# MachNhan.net
KiCad netlist of a schematic drawn in Altium Designer
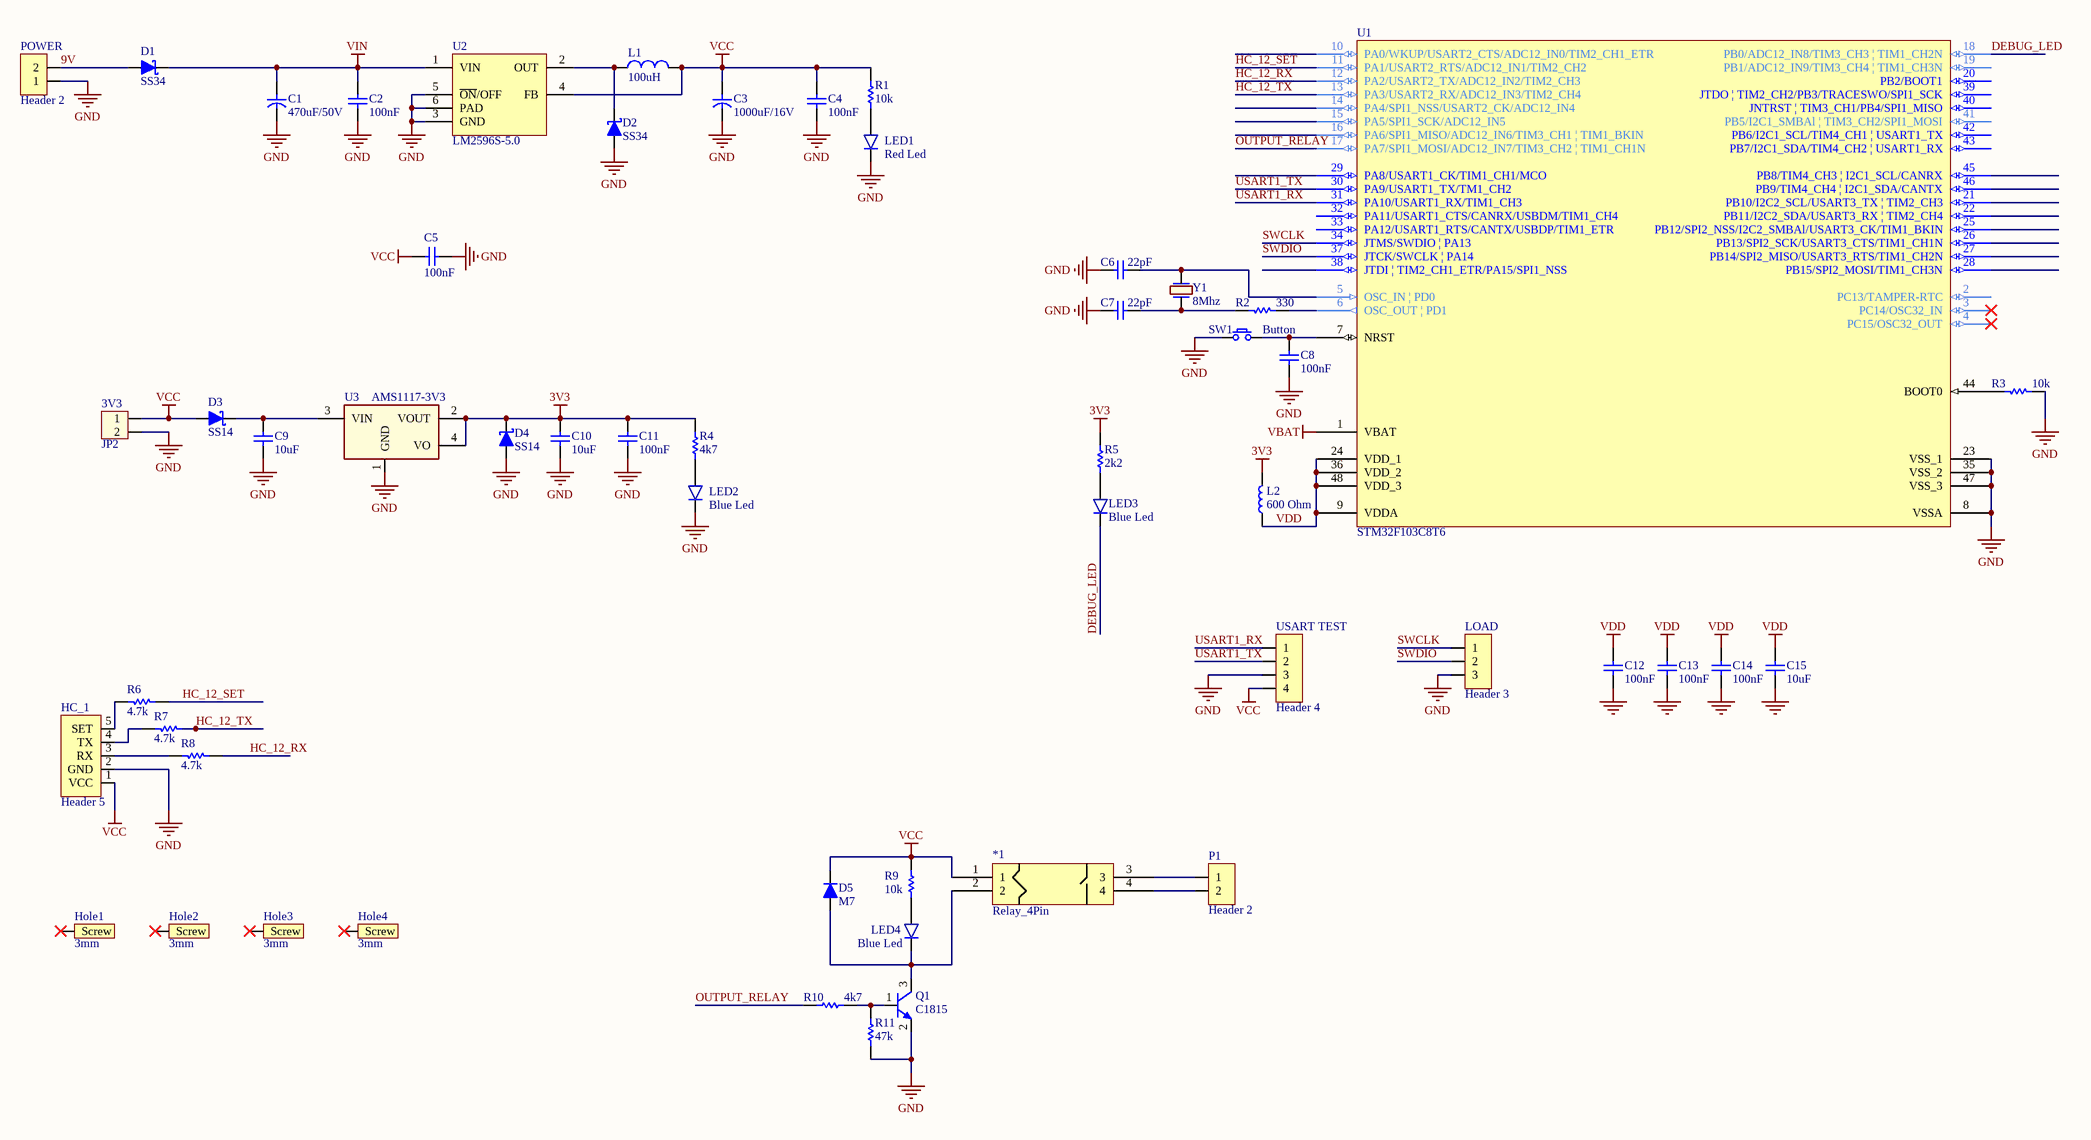
[diagram p0: MachNhan.SchDoc]

(export (version "E")
  (design (tool "Eeschema 10.0.6"))
  (components
    (comp (ref "*1")
      (value "Relay_4Pin")
      (footprint "Relay4 - duplicate")
      (libsource (lib "BKIT4U_LIB") (part "Relay_4Pin"))
    )
    (comp (ref "3V3")
      (value "JP2")
      (footprint "CON Header 2")
      (description "Connector 2")
      (libsource (lib "BKIT4U_LIB") (part "Con2"))
    )
    (comp (ref "C1")
      (value "470uF/50V")
      (footprint "CR/D.10.0x16.0/P.5.0")
      (description "Capacitor pol")
      (libsource (lib "BKIT4U_LIB") (part "Capacitor"))
    )
    (comp (ref "C2")
      (value "100nF")
      (footprint "C 0805 (2012)")
      (description "Capacitor non-pol")
      (libsource (lib "BKIT4U_LIB") (part "Capacitor NP"))
    )
    (comp (ref "C3")
      (value "1000uF/16V")
      (footprint "CR/D.10.0x12.5/P.5.0")
      (description "Capacitor pol")
      (libsource (lib "BKIT4U_LIB") (part "Capacitor"))
    )
    (comp (ref "C4")
      (value "100nF")
      (footprint "C 0805 (2012)")
      (description "Capacitor non-pol")
      (libsource (lib "BKIT4U_LIB") (part "Capacitor NP"))
    )
    (comp (ref "C5")
      (value "100nF")
      (footprint "C 0805 (2012)")
      (description "Capacitor non-pol")
      (libsource (lib "BKIT4U_LIB") (part "Capacitor NP"))
    )
    (comp (ref "C6")
      (value "22pF")
      (footprint "C 0805 (2012)")
      (description "Capacitor non-pol")
      (libsource (lib "BKIT4U_LIB") (part "Capacitor NP"))
    )
    (comp (ref "C7")
      (value "22pF")
      (footprint "C 0805 (2012)")
      (description "Capacitor non-pol")
      (libsource (lib "BKIT4U_LIB") (part "Capacitor NP"))
    )
    (comp (ref "C8")
      (value "100nF")
      (footprint "C 0805 (2012)")
      (description "Capacitor non-pol")
      (libsource (lib "BKIT4U_LIB") (part "Capacitor NP"))
    )
    (comp (ref "C9")
      (value "10uF")
      (footprint "C 0805 (2012)")
      (description "Capacitor non-pol")
      (libsource (lib "BKIT4U_LIB") (part "Capacitor NP"))
    )
    (comp (ref "C10")
      (value "10uF")
      (footprint "C 0805 (2012)")
      (description "Capacitor non-pol")
      (libsource (lib "BKIT4U_LIB") (part "Capacitor NP"))
    )
    (comp (ref "C11")
      (value "100nF")
      (footprint "C 0805 (2012)")
      (description "Capacitor non-pol")
      (libsource (lib "BKIT4U_LIB") (part "Capacitor NP"))
    )
    (comp (ref "C12")
      (value "100nF")
      (footprint "C 0805 (2012)")
      (description "Capacitor non-pol")
      (libsource (lib "BKIT4U_LIB") (part "Capacitor NP"))
    )
    (comp (ref "C13")
      (value "100nF")
      (footprint "C 0805 (2012)")
      (description "Capacitor non-pol")
      (libsource (lib "BKIT4U_LIB") (part "Capacitor NP"))
    )
    (comp (ref "C14")
      (value "100nF")
      (footprint "C 0805 (2012)")
      (description "Capacitor non-pol")
      (libsource (lib "BKIT4U_LIB") (part "Capacitor NP"))
    )
    (comp (ref "C15")
      (value "10uF")
      (footprint "C 0805 (2012)")
      (description "Capacitor non-pol")
      (libsource (lib "BKIT4U_LIB") (part "Capacitor NP"))
    )
    (comp (ref "D1")
      (value "SS34")
      (footprint "DO-214AC (SMA)")
      (description "Schottky Diode")
      (fields (field (name "PUBLISHER") "Altium Limited"))
      (libsource (lib "BKIT4U_LIB") (part "Diode Schottky"))
    )
    (comp (ref "D2")
      (value "SS34")
      (footprint "DO-214AC (SMA)")
      (description "Schottky Diode")
      (fields (field (name "PUBLISHER") "Altium Limited"))
      (libsource (lib "BKIT4U_LIB") (part "Diode Schottky"))
    )
    (comp (ref "D3")
      (value "SS14")
      (footprint "DO-214AC (SMA)")
      (description "Schottky Diode")
      (fields (field (name "PUBLISHER") "Altium Limited"))
      (libsource (lib "BKIT4U_LIB") (part "Diode Schottky"))
    )
    (comp (ref "D4")
      (value "SS14")
      (footprint "DO-214AC (SMA)")
      (description "Schottky Diode")
      (fields (field (name "PUBLISHER") "Altium Limited"))
      (libsource (lib "BKIT4U_LIB") (part "Diode Schottky"))
    )
    (comp (ref "D5")
      (value "M7")
      (footprint "DO-214AC (SMA)")
      (description "Default Diode")
      (fields (field (name "PUBLISHER") "Altium Limited"))
      (libsource (lib "BKIT4U_LIB") (part "Diode"))
    )
    (comp (ref "HC_1")
      (value "Header 5")
      (footprint "HC_12")
      (description "Header, 5-Pin")
      (fields (field (name "PUBLISHER") "Altium Limited"))
      (libsource (lib "BKIT4U_LIB") (part "HC_12"))
    )
    (comp (ref "Hole1") (value "3mm") (footprint "SCREW/3M/7M") (libsource (lib "BKIT4U_LIB") (part "Screw")))
    (comp (ref "Hole2") (value "3mm") (footprint "SCREW/3M/7M") (libsource (lib "BKIT4U_LIB") (part "Screw")))
    (comp (ref "Hole3") (value "3mm") (footprint "SCREW/3M/7M") (libsource (lib "BKIT4U_LIB") (part "Screw")))
    (comp (ref "Hole4") (value "3mm") (footprint "SCREW/3M/7M") (libsource (lib "BKIT4U_LIB") (part "Screw")))
    (comp (ref "L1")
      (value "100uH")
      (footprint "Inductor SMD 12x12x8")
      (description "Inductor")
      (libsource (lib "syhaunguyen") (part "L1"))
    )
    (comp (ref "L2")
      (value "600 Ohm")
      (footprint "Inductor SMD 0805 (2012)")
      (description "Inductor")
      (libsource (lib "BKIT4U_LIB") (part "Inductor"))
    )
    (comp (ref "LED1")
      (value "Red Led")
      (footprint "Led SMD 0805")
      (description "Typical LED")
      (libsource (lib "BKIT4U_LIB") (part "Led"))
    )
    (comp (ref "LED2")
      (value "Blue Led")
      (footprint "Led SMD 0805")
      (description "Typical LED")
      (libsource (lib "BKIT4U_LIB") (part "Led"))
    )
    (comp (ref "LED3")
      (value "Blue Led")
      (footprint "Led SMD 0805")
      (description "Typical LED")
      (libsource (lib "BKIT4U_LIB") (part "Led"))
    )
    (comp (ref "LED4")
      (value "Blue Led")
      (footprint "Led SMD 0805")
      (description "Typical LED")
      (libsource (lib "BKIT4U_LIB") (part "Led"))
    )
    (comp (ref "LOAD")
      (value "Header 3")
      (footprint "Header 3")
      (description "Header, 3-Pin")
      (libsource (lib "BKIT4U_LIB") (part "Header 3"))
    )
    (comp (ref "P1")
      (value "Header 2")
      (footprint "Header 2")
      (description "Header, 2-Pin")
      (fields (field (name "PUBLISHER") "Altium Limited"))
      (libsource (lib "") (part "Header 2_1"))
    )
    (comp (ref "POWER")
      (value "Header 2")
      (footprint "CON Header 2")
      (description "Header, 2-Pin")
      (fields (field (name "PUBLISHER") "Altium Limited"))
      (libsource (lib "BKIT4U_LIB") (part "Header 2"))
    )
    (comp (ref "Q1")
      (value "C1815")
      (footprint "SOT-23")
      (description "NPN Bipolar Transistor")
      (libsource (lib "BKIT4U_LIB") (part "Transistor NPN"))
    )
    (comp (ref "R1")
      (value "10k")
      (footprint "R 0805 (2012)")
      (description "Resistor")
      (fields (field (name "PUBLISHER") "Altium Limited"))
      (libsource (lib "BKIT4U_LIB") (part "Resistor"))
    )
    (comp (ref "R2")
      (value "330")
      (footprint "R 0805 (2012)")
      (description "Resistor")
      (fields (field (name "PUBLISHER") "Altium Limited"))
      (libsource (lib "BKIT4U_LIB") (part "Resistor"))
    )
    (comp (ref "R3")
      (value "10k")
      (footprint "R 0805 (2012)")
      (description "Resistor")
      (fields (field (name "PUBLISHER") "Altium Limited"))
      (libsource (lib "BKIT4U_LIB") (part "Resistor"))
    )
    (comp (ref "R4")
      (value "4k7")
      (footprint "R 0805 (2012)")
      (description "Resistor")
      (fields (field (name "PUBLISHER") "Altium Limited"))
      (libsource (lib "BKIT4U_LIB") (part "Resistor"))
    )
    (comp (ref "R5")
      (value "2k2")
      (footprint "R 0805 (2012)")
      (description "Resistor")
      (fields (field (name "PUBLISHER") "Altium Limited"))
      (libsource (lib "BKIT4U_LIB") (part "Resistor"))
    )
    (comp (ref "R6")
      (value "4.7k")
      (footprint "R 0805 (2012)")
      (description "Resistor")
      (fields (field (name "PUBLISHER") "Altium Limited"))
      (libsource (lib "BKIT4U_LIB") (part "Resistor"))
    )
    (comp (ref "R7")
      (value "4.7k")
      (footprint "R 0805 (2012)")
      (description "Resistor")
      (fields (field (name "PUBLISHER") "Altium Limited"))
      (libsource (lib "BKIT4U_LIB") (part "Resistor"))
    )
    (comp (ref "R8")
      (value "4.7k")
      (footprint "R 0805 (2012)")
      (description "Resistor")
      (fields (field (name "PUBLISHER") "Altium Limited"))
      (libsource (lib "BKIT4U_LIB") (part "Resistor"))
    )
    (comp (ref "R9")
      (value "10k")
      (footprint "R 0805 (2012)")
      (description "Resistor")
      (fields (field (name "PUBLISHER") "Altium Limited"))
      (libsource (lib "BKIT4U_LIB") (part "Resistor"))
    )
    (comp (ref "R10")
      (value "4k7")
      (footprint "R 0805 (2012)")
      (description "Resistor")
      (fields (field (name "PUBLISHER") "Altium Limited"))
      (libsource (lib "BKIT4U_LIB") (part "Resistor"))
    )
    (comp (ref "R11")
      (value "47k")
      (footprint "R 0805 (2012)")
      (description "Resistor")
      (fields (field (name "PUBLISHER") "Altium Limited"))
      (libsource (lib "BKIT4U_LIB") (part "Resistor"))
    )
    (comp (ref "SW1")
      (value "Button")
      (footprint "SW/2/SMD")
      (description "Tact switch 2 pin")
      (libsource (lib "BKIT4U_LIB") (part "SW SPST"))
    )
    (comp (ref "U1")
      (value "STM32F103C8T6")
      (footprint "LQFP48_N")
      (description "STM32 ARM-based 32-bit MCU with 64 Kbytes Flash, 48-pin LQFP, Industrial Temperature")
      (fields (field (name "PUBLISHER") "Altium Limited"))
      (libsource (lib "BKIT4U_LIB") (part "STM32F103C8T6"))
    )
    (comp (ref "U2")
      (value "LM2596S-5.0")
      (footprint "TO-263-5")
      (description "SIMPLE SWITCHER® 3A Step-Down Voltage Regulator")
      (libsource (lib "BKIT4U_LIB") (part "LM2576/96"))
    )
    (comp (ref "U3")
      (value "AMS1117-3V3")
      (footprint "SOT-223")
      (description "1A LDO Voltage Regulator, ADJ or fixed 1.5/1.8/2.5/2.85/3.3/5V")
      (libsource (lib "BKIT4U_LIB") (part "AMS1117"))
    )
    (comp (ref "USART TEST")
      (value "Header 4")
      (footprint "CON Header 4")
      (description "Header, 4-Pin")
      (libsource (lib "BKIT4U_LIB") (part "Header 4"))
    )
    (comp (ref "Y1")
      (value "8Mhz")
      (footprint "Crystal HC49US SMD")
      (libsource (lib "BKIT4U_LIB") (part "Crystal"))
    )
  )
  (nets
    (net (code "1") (name "/9V") (class "Default")
      (node (ref "D1") (pin "1") (pinfunction "A_1") (pintype "passive"))
      (node (ref "POWER") (pin "2") (pinfunction "2_2") (pintype "passive"))
    )
    (net (code "2") (name "/DEBUG_LED") (class "Default")
      (node (ref "LED3") (pin "2") (pinfunction "K_2") (pintype "passive"))
      (node (ref "U1") (pin "18") (pinfunction "PB0/ADC12_IN8/TIM3_CH3_¦_TIM1_CH2N_18") (pintype "bidirectional"))
    )
    (net (code "3") (name "/HC_12_RX") (class "Default")
      (node (ref "R8") (pin "2") (pinfunction "2_2") (pintype "passive"))
      (node (ref "U1") (pin "12") (pinfunction "PA2/USART2_TX/ADC12_IN2/TIM2_CH3_12") (pintype "bidirectional"))
    )
    (net (code "4") (name "/HC_12_SET") (class "Default")
      (node (ref "R6") (pin "2") (pinfunction "2_2") (pintype "passive"))
      (node (ref "U1") (pin "11") (pinfunction "PA1/USART2_RTS/ADC12_IN1/TIM2_CH2_11") (pintype "bidirectional"))
    )
    (net (code "5") (name "/HC_12_TX") (class "Default")
      (node (ref "R7") (pin "2") (pinfunction "2_2") (pintype "passive"))
      (node (ref "U1") (pin "13") (pinfunction "PA3/USART2_RX/ADC12_IN3/TIM2_CH4_13") (pintype "bidirectional"))
    )
    (net (code "6") (name "/OUTPUT_RELAY") (class "Default")
      (node (ref "R10") (pin "1") (pinfunction "1_1") (pintype "passive"))
      (node (ref "U1") (pin "17") (pinfunction "PA7/SPI1_MOSI/ADC12_IN7/TIM3_CH2_¦_TIM1_CH1N_17") (pintype "bidirectional"))
    )
    (net (code "7") (name "/SWCLK") (class "Default")
      (node (ref "LOAD") (pin "1") (pinfunction "1_1") (pintype "passive"))
      (node (ref "U1") (pin "34") (pinfunction "JTMS/SWDIO_¦_PA13_34") (pintype "bidirectional"))
    )
    (net (code "8") (name "/SWDIO") (class "Default")
      (node (ref "LOAD") (pin "2") (pinfunction "2_2") (pintype "passive"))
      (node (ref "U1") (pin "37") (pinfunction "JTCK/SWCLK_¦_PA14_37") (pintype "bidirectional"))
    )
    (net (code "9") (name "/USART1_RX") (class "Default")
      (node (ref "U1") (pin "31") (pinfunction "PA10/USART1_RX/TIM1_CH3_31") (pintype "bidirectional"))
      (node (ref "USART TEST") (pin "1") (pinfunction "1_1") (pintype "passive"))
    )
    (net (code "10") (name "/USART1_TX") (class "Default")
      (node (ref "U1") (pin "30") (pinfunction "PA9/USART1_TX/TM1_CH2_30") (pintype "bidirectional"))
      (node (ref "USART TEST") (pin "2") (pinfunction "2_2") (pintype "passive"))
    )
    (net (code "11") (name "3V3") (class "Default")
      (node (ref "C10") (pin "1") (pinfunction "1_1") (pintype "passive"))
      (node (ref "C11") (pin "1") (pinfunction "1_1") (pintype "passive"))
      (node (ref "D4") (pin "2") (pinfunction "K_2") (pintype "passive"))
      (node (ref "L2") (pin "2") (pinfunction "2_2") (pintype "passive"))
      (node (ref "R4") (pin "2") (pinfunction "2_2") (pintype "passive"))
      (node (ref "R5") (pin "2") (pinfunction "2_2") (pintype "passive"))
      (node (ref "U3") (pin "2") (pinfunction "VOUT_2") (pintype "passive"))
      (node (ref "U3") (pin "4") (pinfunction "VO_4") (pintype "passive"))
    )
    (net (code "12") (name "GND") (class "Default")
      (node (ref "3V3") (pin "2") (pinfunction "2_2") (pintype "passive"))
      (node (ref "C1") (pin "2") (pinfunction "2_2") (pintype "passive"))
      (node (ref "C10") (pin "2") (pinfunction "2_2") (pintype "passive"))
      (node (ref "C11") (pin "2") (pinfunction "2_2") (pintype "passive"))
      (node (ref "C12") (pin "2") (pinfunction "2_2") (pintype "passive"))
      (node (ref "C13") (pin "2") (pinfunction "2_2") (pintype "passive"))
      (node (ref "C14") (pin "2") (pinfunction "2_2") (pintype "passive"))
      (node (ref "C15") (pin "2") (pinfunction "2_2") (pintype "passive"))
      (node (ref "C2") (pin "2") (pinfunction "2_2") (pintype "passive"))
      (node (ref "C3") (pin "2") (pinfunction "2_2") (pintype "passive"))
      (node (ref "C4") (pin "2") (pinfunction "2_2") (pintype "passive"))
      (node (ref "C5") (pin "1") (pinfunction "1_1") (pintype "passive"))
      (node (ref "C6") (pin "2") (pinfunction "2_2") (pintype "passive"))
      (node (ref "C7") (pin "2") (pinfunction "2_2") (pintype "passive"))
      (node (ref "C8") (pin "2") (pinfunction "2_2") (pintype "passive"))
      (node (ref "C9") (pin "2") (pinfunction "2_2") (pintype "passive"))
      (node (ref "D2") (pin "1") (pinfunction "A_1") (pintype "passive"))
      (node (ref "D4") (pin "1") (pinfunction "A_1") (pintype "passive"))
      (node (ref "HC_1") (pin "2") (pinfunction "GND_2") (pintype "passive"))
      (node (ref "LED1") (pin "2") (pinfunction "K_2") (pintype "passive"))
      (node (ref "LED2") (pin "2") (pinfunction "K_2") (pintype "passive"))
      (node (ref "LOAD") (pin "3") (pinfunction "3_3") (pintype "passive"))
      (node (ref "POWER") (pin "1") (pinfunction "1_1") (pintype "passive"))
      (node (ref "Q1") (pin "2") (pinfunction "E_2") (pintype "passive"))
      (node (ref "R11") (pin "1") (pinfunction "1_1") (pintype "passive"))
      (node (ref "R3") (pin "1") (pinfunction "1_1") (pintype "passive"))
      (node (ref "SW1") (pin "1") (pinfunction "1_1") (pintype "passive"))
      (node (ref "U1") (pin "23") (pinfunction "VSS_1_23") (pintype "power_in"))
      (node (ref "U1") (pin "35") (pinfunction "VSS_2_35") (pintype "power_in"))
      (node (ref "U1") (pin "47") (pinfunction "VSS_3_47") (pintype "power_in"))
      (node (ref "U1") (pin "8") (pinfunction "VSSA_8") (pintype "power_in"))
      (node (ref "U2") (pin "3") (pinfunction "GND_3") (pintype "passive"))
      (node (ref "U2") (pin "5") (pinfunction "~{ON}/OFF_5") (pintype "passive"))
      (node (ref "U2") (pin "6") (pinfunction "PAD_6") (pintype "passive"))
      (node (ref "U3") (pin "1") (pinfunction "GND_1") (pintype "passive"))
      (node (ref "USART TEST") (pin "3") (pinfunction "3_3") (pintype "passive"))
    )
    (net (code "13") (name "Net-(*1-Pad3)") (class "Default")
      (node (ref "*1") (pin "3") (pinfunction "3_3") (pintype "passive"))
      (node (ref "P1") (pin "1") (pinfunction "1_1") (pintype "passive"))
    )
    (net (code "14") (name "Net-(*1-Pad4)") (class "Default")
      (node (ref "*1") (pin "4") (pinfunction "4_4") (pintype "passive"))
      (node (ref "P1") (pin "2") (pinfunction "2_2") (pintype "passive"))
    )
    (net (code "15") (name "Net-(C7-Pad1)") (class "Default")
      (node (ref "C7") (pin "1") (pinfunction "1_1") (pintype "passive"))
      (node (ref "R2") (pin "2") (pinfunction "2_2") (pintype "passive"))
      (node (ref "Y1") (pin "1") (pinfunction "1_1") (pintype "passive"))
    )
    (net (code "16") (name "Net-(D2-K)") (class "Default")
      (node (ref "D2") (pin "2") (pinfunction "K_2") (pintype "passive"))
      (node (ref "L1") (pin "1") (pinfunction "1_1") (pintype "passive"))
      (node (ref "U2") (pin "2") (pinfunction "OUT_2") (pintype "passive"))
    )
    (net (code "17") (name "Net-(D3-K)") (class "Default")
      (node (ref "C9") (pin "1") (pinfunction "1_1") (pintype "passive"))
      (node (ref "D3") (pin "2") (pinfunction "K_2") (pintype "passive"))
      (node (ref "U3") (pin "3") (pinfunction "VIN_3") (pintype "power_in"))
    )
    (net (code "18") (name "Net-(D5-A)") (class "Default")
      (node (ref "*1") (pin "2") (pinfunction "2_2") (pintype "passive"))
      (node (ref "D5") (pin "1") (pinfunction "A_1") (pintype "passive"))
      (node (ref "LED4") (pin "2") (pinfunction "K_2") (pintype "passive"))
      (node (ref "Q1") (pin "3") (pinfunction "C_3") (pintype "passive"))
    )
    (net (code "19") (name "Net-(HC_1-RX)") (class "Default")
      (node (ref "HC_1") (pin "3") (pinfunction "RX_3") (pintype "passive"))
      (node (ref "R8") (pin "1") (pinfunction "1_1") (pintype "passive"))
    )
    (net (code "20") (name "Net-(HC_1-SET)") (class "Default")
      (node (ref "HC_1") (pin "5") (pinfunction "SET_5") (pintype "passive"))
      (node (ref "R6") (pin "1") (pinfunction "1_1") (pintype "passive"))
    )
    (net (code "21") (name "Net-(HC_1-TX)") (class "Default")
      (node (ref "HC_1") (pin "4") (pinfunction "TX_4") (pintype "passive"))
      (node (ref "R7") (pin "1") (pinfunction "1_1") (pintype "passive"))
    )
    (net (code "22") (name "Net-(LED1-A)") (class "Default")
      (node (ref "LED1") (pin "1") (pinfunction "A_1") (pintype "passive"))
      (node (ref "R1") (pin "1") (pinfunction "1_1") (pintype "passive"))
    )
    (net (code "23") (name "Net-(LED2-A)") (class "Default")
      (node (ref "LED2") (pin "1") (pinfunction "A_1") (pintype "passive"))
      (node (ref "R4") (pin "1") (pinfunction "1_1") (pintype "passive"))
    )
    (net (code "24") (name "Net-(LED3-A)") (class "Default")
      (node (ref "LED3") (pin "1") (pinfunction "A_1") (pintype "passive"))
      (node (ref "R5") (pin "1") (pinfunction "1_1") (pintype "passive"))
    )
    (net (code "25") (name "Net-(LED4-A)") (class "Default")
      (node (ref "LED4") (pin "1") (pinfunction "A_1") (pintype "passive"))
      (node (ref "R9") (pin "1") (pinfunction "1_1") (pintype "passive"))
    )
    (net (code "26") (name "Net-(Q1-B)") (class "Default")
      (node (ref "Q1") (pin "1") (pinfunction "B_1") (pintype "passive"))
      (node (ref "R10") (pin "2") (pinfunction "2_2") (pintype "passive"))
      (node (ref "R11") (pin "2") (pinfunction "2_2") (pintype "passive"))
    )
    (net (code "27") (name "Net-(U1-BOOT0)") (class "Default")
      (node (ref "R3") (pin "2") (pinfunction "2_2") (pintype "passive"))
      (node (ref "U1") (pin "44") (pinfunction "BOOT0_44") (pintype "input"))
    )
    (net (code "28") (name "Net-(U1-NRST)") (class "Default")
      (node (ref "C8") (pin "1") (pinfunction "1_1") (pintype "passive"))
      (node (ref "SW1") (pin "2") (pinfunction "2_2") (pintype "passive"))
      (node (ref "U1") (pin "7") (pinfunction "NRST_7") (pintype "bidirectional"))
    )
    (net (code "29") (name "Net-(U1-OSC_IN_¦_PD0)") (class "Default")
      (node (ref "C6") (pin "1") (pinfunction "1_1") (pintype "passive"))
      (node (ref "U1") (pin "5") (pinfunction "OSC_IN_¦_PD0_5") (pintype "input"))
      (node (ref "Y1") (pin "2") (pinfunction "2_2") (pintype "passive"))
    )
    (net (code "30") (name "Net-(U1-OSC_OUT_¦_PD1)") (class "Default")
      (node (ref "R2") (pin "1") (pinfunction "1_1") (pintype "passive"))
      (node (ref "U1") (pin "6") (pinfunction "OSC_OUT_¦_PD1_6") (pintype "output"))
    )
    (net (code "31") (name "VBAT") (class "Default")
      (node (ref "U1") (pin "1") (pinfunction "VBAT_1") (pintype "power_in"))
    )
    (net (code "32") (name "VCC") (class "Default")
      (node (ref "*1") (pin "1") (pinfunction "1_1") (pintype "passive"))
      (node (ref "3V3") (pin "1") (pinfunction "1_1") (pintype "passive"))
      (node (ref "C3") (pin "1") (pinfunction "1_1") (pintype "passive"))
      (node (ref "C4") (pin "1") (pinfunction "1_1") (pintype "passive"))
      (node (ref "C5") (pin "2") (pinfunction "2_2") (pintype "passive"))
      (node (ref "D3") (pin "1") (pinfunction "A_1") (pintype "passive"))
      (node (ref "D5") (pin "2") (pinfunction "K_2") (pintype "passive"))
      (node (ref "HC_1") (pin "1") (pinfunction "VCC_1") (pintype "passive"))
      (node (ref "L1") (pin "2") (pinfunction "2_2") (pintype "passive"))
      (node (ref "R1") (pin "2") (pinfunction "2_2") (pintype "passive"))
      (node (ref "R9") (pin "2") (pinfunction "2_2") (pintype "passive"))
      (node (ref "U2") (pin "4") (pinfunction "FB_4") (pintype "passive"))
      (node (ref "USART TEST") (pin "4") (pinfunction "4_4") (pintype "passive"))
    )
    (net (code "33") (name "VDD") (class "Default")
      (node (ref "C12") (pin "1") (pinfunction "1_1") (pintype "passive"))
      (node (ref "C13") (pin "1") (pinfunction "1_1") (pintype "passive"))
      (node (ref "C14") (pin "1") (pinfunction "1_1") (pintype "passive"))
      (node (ref "C15") (pin "1") (pinfunction "1_1") (pintype "passive"))
      (node (ref "L2") (pin "1") (pinfunction "1_1") (pintype "passive"))
      (node (ref "U1") (pin "24") (pinfunction "VDD_1_24") (pintype "power_in"))
      (node (ref "U1") (pin "36") (pinfunction "VDD_2_36") (pintype "power_in"))
      (node (ref "U1") (pin "48") (pinfunction "VDD_3_48") (pintype "power_in"))
      (node (ref "U1") (pin "9") (pinfunction "VDDA_9") (pintype "power_in"))
    )
    (net (code "34") (name "VIN") (class "Default")
      (node (ref "C1") (pin "1") (pinfunction "1_1") (pintype "passive"))
      (node (ref "C2") (pin "1") (pinfunction "1_1") (pintype "passive"))
      (node (ref "D1") (pin "2") (pinfunction "K_2") (pintype "passive"))
      (node (ref "U2") (pin "1") (pinfunction "VIN_1") (pintype "passive"))
    )
    (net (code "35") (name "unconnected-(Hole1-Screw-Pad1)") (class "Default")
      (node (ref "Hole1") (pin "1") (pinfunction "Screw_1") (pintype "passive+no_connect"))
    )
    (net (code "36") (name "unconnected-(Hole2-Screw-Pad1)") (class "Default")
      (node (ref "Hole2") (pin "1") (pinfunction "Screw_1") (pintype "passive+no_connect"))
    )
    (net (code "37") (name "unconnected-(Hole3-Screw-Pad1)") (class "Default")
      (node (ref "Hole3") (pin "1") (pinfunction "Screw_1") (pintype "passive+no_connect"))
    )
    (net (code "38") (name "unconnected-(Hole4-Screw-Pad1)") (class "Default")
      (node (ref "Hole4") (pin "1") (pinfunction "Screw_1") (pintype "passive+no_connect"))
    )
    (net (code "39") (name "unconnected-(U1-JNTRST_¦_TIM3_CH1{slash}PB4{slash}SPI1_MISO-Pad40)") (class "Default")
      (node (ref "U1") (pin "40") (pinfunction "JNTRST_¦_TIM3_CH1/PB4/SPI1_MISO_40") (pintype "bidirectional"))
    )
    (net (code "40") (name "unconnected-(U1-JTDI_¦_TIM2_CH1_ETR{slash}PA15{slash}SPI1_NSS-Pad38)") (class "Default")
      (node (ref "U1") (pin "38") (pinfunction "JTDI_¦_TIM2_CH1_ETR/PA15/SPI1_NSS_38") (pintype "bidirectional"))
    )
    (net (code "41") (name "unconnected-(U1-JTDO_¦_TIM2_CH2{slash}PB3{slash}TRACESWO{slash}SPI1_SCK-Pad39)") (class "Default")
      (node (ref "U1") (pin "39") (pinfunction "JTDO_¦_TIM2_CH2/PB3/TRACESWO/SPI1_SCK_39") (pintype "bidirectional"))
    )
    (net (code "42") (name "unconnected-(U1-PA0{slash}WKUP{slash}USART2_CTS{slash}ADC12_IN0{slash}TIM2_CH1_ETR-Pad10)") (class "Default")
      (node (ref "U1") (pin "10") (pinfunction "PA0/WKUP/USART2_CTS/ADC12_IN0/TIM2_CH1_ETR_10") (pintype "bidirectional"))
    )
    (net (code "43") (name "unconnected-(U1-PA4{slash}SPI1_NSS{slash}USART2_CK{slash}ADC12_IN4-Pad14)") (class "Default")
      (node (ref "U1") (pin "14") (pinfunction "PA4/SPI1_NSS/USART2_CK/ADC12_IN4_14") (pintype "bidirectional"))
    )
    (net (code "44") (name "unconnected-(U1-PA5{slash}SPI1_SCK{slash}ADC12_IN5-Pad15)") (class "Default")
      (node (ref "U1") (pin "15") (pinfunction "PA5/SPI1_SCK/ADC12_IN5_15") (pintype "bidirectional"))
    )
    (net (code "45") (name "unconnected-(U1-PA6{slash}SPI1_MISO{slash}ADC12_IN6{slash}TIM3_CH1_¦_TIM1_BKIN-Pad16)") (class "Default")
      (node (ref "U1") (pin "16") (pinfunction "PA6/SPI1_MISO/ADC12_IN6/TIM3_CH1_¦_TIM1_BKIN_16") (pintype "bidirectional"))
    )
    (net (code "46") (name "unconnected-(U1-PA8{slash}USART1_CK{slash}TIM1_CH1{slash}MCO-Pad29)") (class "Default")
      (node (ref "U1") (pin "29") (pinfunction "PA8/USART1_CK/TIM1_CH1/MCO_29") (pintype "bidirectional"))
    )
    (net (code "47") (name "unconnected-(U1-PA11{slash}USART1_CTS{slash}CANRX{slash}USBDM{slash}TIM1_CH4-Pad32)") (class "Default")
      (node (ref "U1") (pin "32") (pinfunction "PA11/USART1_CTS/CANRX/USBDM/TIM1_CH4_32") (pintype "bidirectional"))
    )
    (net (code "48") (name "unconnected-(U1-PA12{slash}USART1_RTS{slash}CANTX{slash}USBDP{slash}TIM1_ETR-Pad33)") (class "Default")
      (node (ref "U1") (pin "33") (pinfunction "PA12/USART1_RTS/CANTX/USBDP/TIM1_ETR_33") (pintype "bidirectional"))
    )
    (net (code "49") (name "unconnected-(U1-PB1{slash}ADC12_IN9{slash}TIM3_CH4_¦_TIM1_CH3N-Pad19)") (class "Default")
      (node (ref "U1") (pin "19") (pinfunction "PB1/ADC12_IN9/TIM3_CH4_¦_TIM1_CH3N_19") (pintype "bidirectional"))
    )
    (net (code "50") (name "unconnected-(U1-PB2{slash}BOOT1-Pad20)") (class "Default")
      (node (ref "U1") (pin "20") (pinfunction "PB2/BOOT1_20") (pintype "bidirectional"))
    )
    (net (code "51") (name "unconnected-(U1-PB5{slash}I2C1_SMBAl_¦_TIM3_CH2{slash}SPI1_MOSI-Pad41)") (class "Default")
      (node (ref "U1") (pin "41") (pinfunction "PB5/I2C1_SMBAl_¦_TIM3_CH2/SPI1_MOSI_41") (pintype "bidirectional"))
    )
    (net (code "52") (name "unconnected-(U1-PB6{slash}I2C1_SCL{slash}TIM4_CH1_¦_USART1_TX-Pad42)") (class "Default")
      (node (ref "U1") (pin "42") (pinfunction "PB6/I2C1_SCL/TIM4_CH1_¦_USART1_TX_42") (pintype "bidirectional"))
    )
    (net (code "53") (name "unconnected-(U1-PB7{slash}I2C1_SDA{slash}TIM4_CH2_¦_USART1_RX-Pad43)") (class "Default")
      (node (ref "U1") (pin "43") (pinfunction "PB7/I2C1_SDA/TIM4_CH2_¦_USART1_RX_43") (pintype "bidirectional"))
    )
    (net (code "54") (name "unconnected-(U1-PB8{slash}TIM4_CH3_¦_I2C1_SCL{slash}CANRX-Pad45)") (class "Default")
      (node (ref "U1") (pin "45") (pinfunction "PB8/TIM4_CH3_¦_I2C1_SCL/CANRX_45") (pintype "bidirectional"))
    )
    (net (code "55") (name "unconnected-(U1-PB9{slash}TIM4_CH4_¦_I2C1_SDA{slash}CANTX-Pad46)") (class "Default")
      (node (ref "U1") (pin "46") (pinfunction "PB9/TIM4_CH4_¦_I2C1_SDA/CANTX_46") (pintype "bidirectional"))
    )
    (net (code "56") (name "unconnected-(U1-PB10{slash}I2C2_SCL{slash}USART3_TX_¦_TIM2_CH3-Pad21)") (class "Default")
      (node (ref "U1") (pin "21") (pinfunction "PB10/I2C2_SCL/USART3_TX_¦_TIM2_CH3_21") (pintype "bidirectional"))
    )
    (net (code "57") (name "unconnected-(U1-PB11{slash}I2C2_SDA{slash}USART3_RX_¦_TIM2_CH4-Pad22)") (class "Default")
      (node (ref "U1") (pin "22") (pinfunction "PB11/I2C2_SDA/USART3_RX_¦_TIM2_CH4_22") (pintype "bidirectional"))
    )
    (net (code "58") (name "unconnected-(U1-PB12{slash}SPI2_NSS{slash}I2C2_SMBAl{slash}USART3_CK{slash}TIM1_BKIN-Pad25)") (class "Default")
      (node (ref "U1") (pin "25") (pinfunction "PB12/SPI2_NSS/I2C2_SMBAl/USART3_CK/TIM1_BKIN_25") (pintype "bidirectional"))
    )
    (net (code "59") (name "unconnected-(U1-PB13{slash}SPI2_SCK{slash}USART3_CTS{slash}TIM1_CH1N-Pad26)") (class "Default")
      (node (ref "U1") (pin "26") (pinfunction "PB13/SPI2_SCK/USART3_CTS/TIM1_CH1N_26") (pintype "bidirectional"))
    )
    (net (code "60") (name "unconnected-(U1-PB14{slash}SPI2_MISO{slash}USART3_RTS{slash}TIM1_CH2N-Pad27)") (class "Default")
      (node (ref "U1") (pin "27") (pinfunction "PB14/SPI2_MISO/USART3_RTS/TIM1_CH2N_27") (pintype "bidirectional"))
    )
    (net (code "61") (name "unconnected-(U1-PB15{slash}SPI2_MOSI{slash}TIM1_CH3N-Pad28)") (class "Default")
      (node (ref "U1") (pin "28") (pinfunction "PB15/SPI2_MOSI/TIM1_CH3N_28") (pintype "bidirectional"))
    )
    (net (code "62") (name "unconnected-(U1-PC13{slash}TAMPER-RTC-Pad2)") (class "Default")
      (node (ref "U1") (pin "2") (pinfunction "PC13/TAMPER-RTC_2") (pintype "bidirectional"))
    )
    (net (code "63") (name "unconnected-(U1-PC14{slash}OSC32_IN-Pad3)") (class "Default")
      (node (ref "U1") (pin "3") (pinfunction "PC14/OSC32_IN_3") (pintype "bidirectional+no_connect"))
    )
    (net (code "64") (name "unconnected-(U1-PC15{slash}OSC32_OUT-Pad4)") (class "Default")
      (node (ref "U1") (pin "4") (pinfunction "PC15/OSC32_OUT_4") (pintype "bidirectional+no_connect"))
    )
    (net (code "65") (name "unconnected-(U2-GND-Pad6)") (class "Default")
      (node (ref "U2") (pin "6") (pinfunction "GND_6") (pintype "passive"))
    )
  )
)
